# Sheet1.net
KiCad netlist of a schematic drawn in Altium Designer
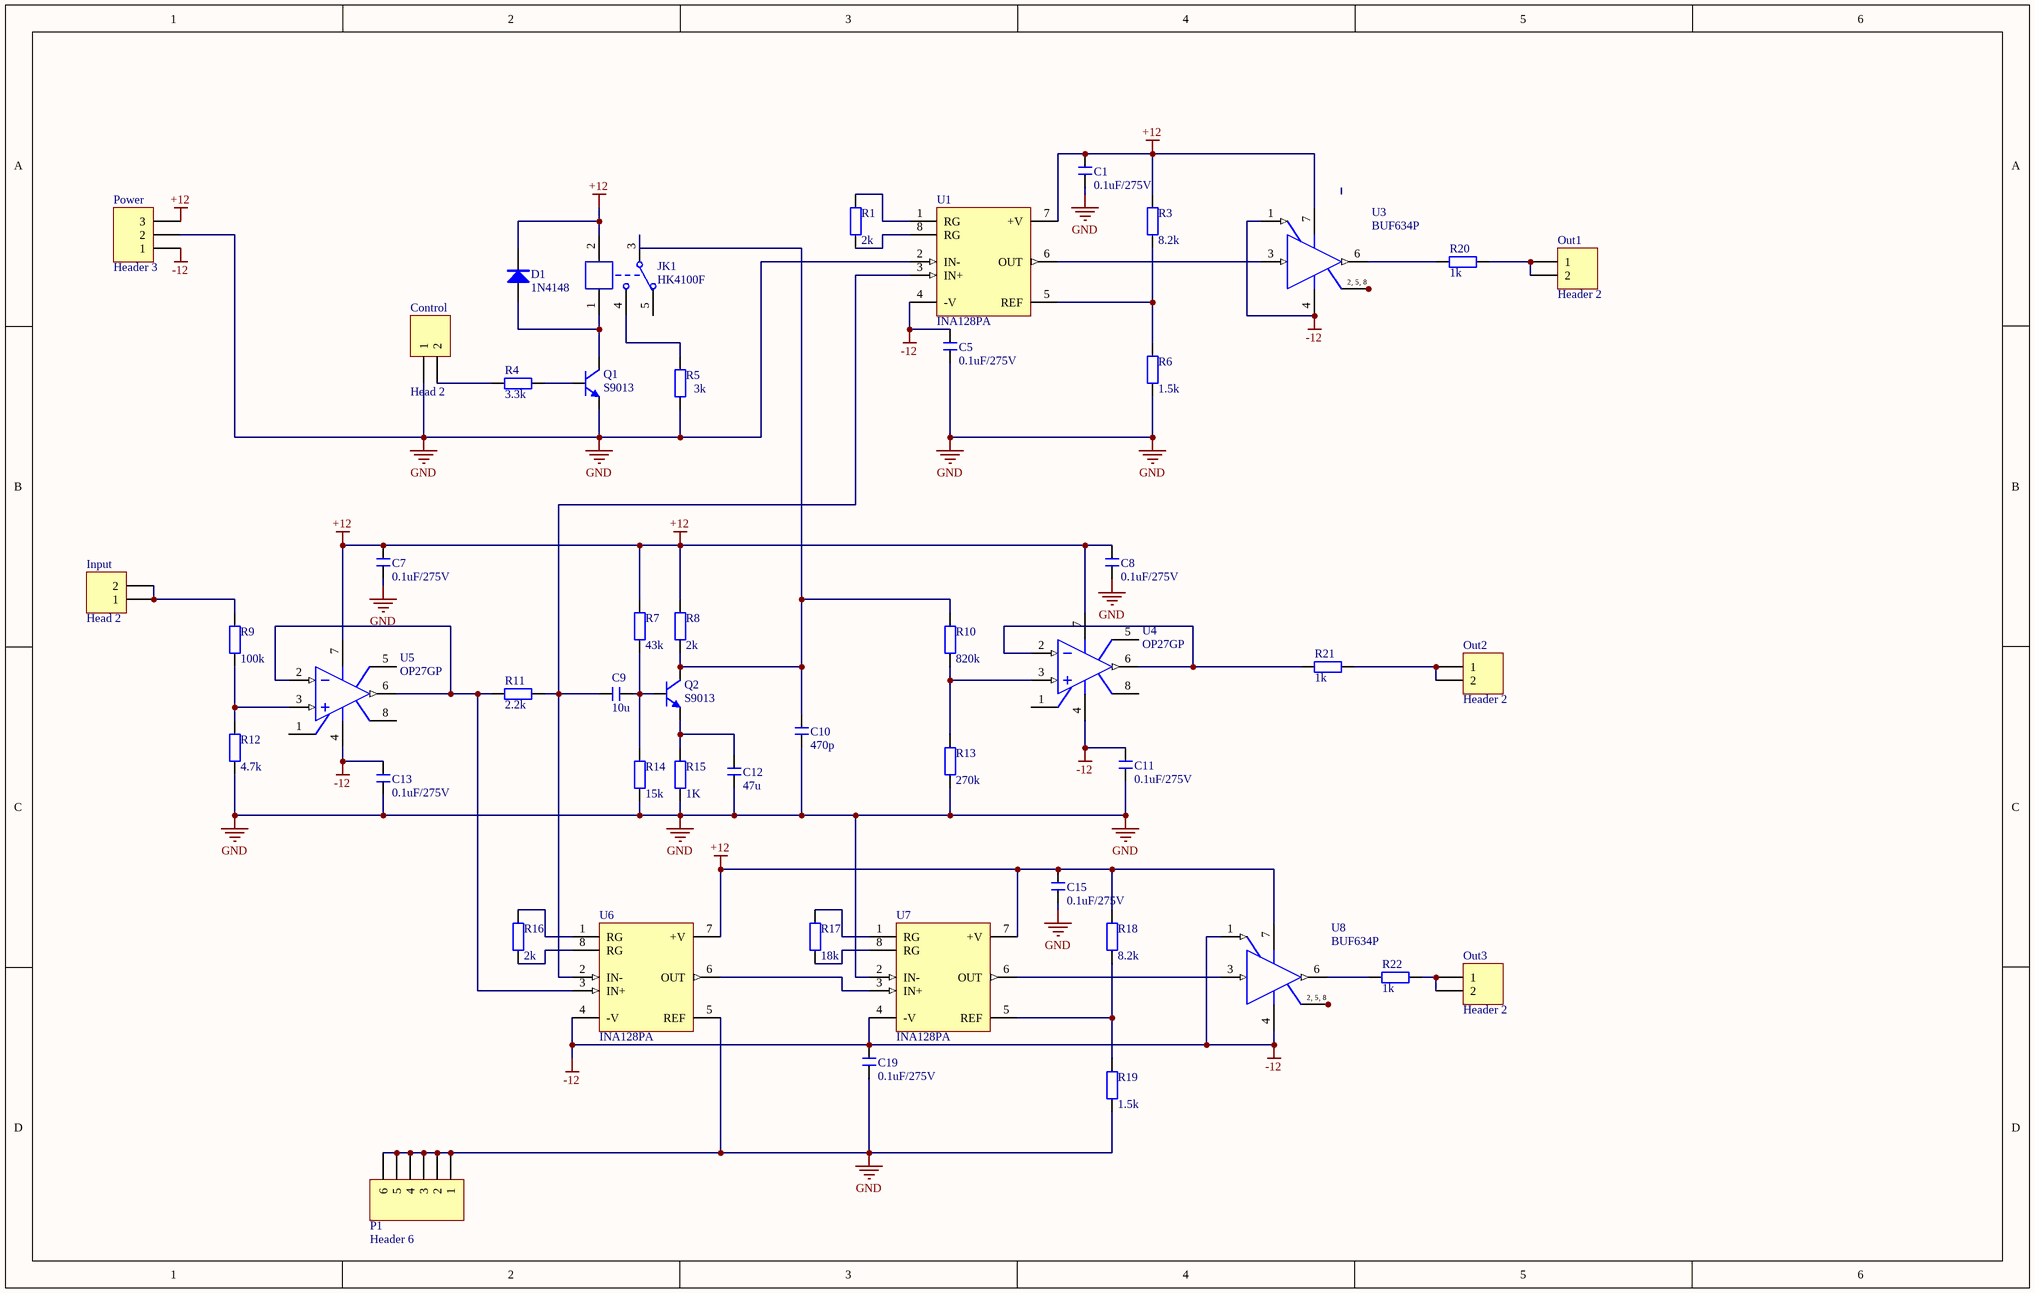
[diagram p0: Sheet1.SchDoc]

(export (version "E")
  (design (tool "Eeschema 10.0.6"))
  (components
    (comp (ref "C1")
      (value "0.1uF/275V")
      (footprint "CBB-CL71")
      (description "CBB电容")
      (fields (field (name "版权归属") "源创客"))
      (libsource (lib "3.1   - 电阻-电容-电感") (part "C-CBB"))
    )
    (comp (ref "C5")
      (value "0.1uF/275V")
      (footprint "CBB-CL71")
      (description "CBB电容")
      (fields (field (name "版权归属") "源创客"))
      (libsource (lib "3.1   - 电阻-电容-电感") (part "C-CBB"))
    )
    (comp (ref "C7")
      (value "0.1uF/275V")
      (footprint "CBB-CL71")
      (description "CBB电容")
      (fields (field (name "版权归属") "源创客"))
      (libsource (lib "3.1   - 电阻-电容-电感") (part "C-CBB"))
    )
    (comp (ref "C8")
      (value "0.1uF/275V")
      (footprint "CBB-CL71")
      (description "CBB电容")
      (fields (field (name "版权归属") "源创客"))
      (libsource (lib "3.1   - 电阻-电容-电感") (part "C-CBB"))
    )
    (comp (ref "C9")
      (value "10u")
      (footprint "CBB-CL71")
      (description "CBB电容")
      (fields (field (name "版权归属") "源创客"))
      (libsource (lib "3.1   - 电阻-电容-电感") (part "C-CBB"))
    )
    (comp (ref "C10")
      (value "470p")
      (footprint "CBB-CL71")
      (description "CBB电容")
      (fields (field (name "版权归属") "源创客"))
      (libsource (lib "3.1   - 电阻-电容-电感") (part "C-CBB"))
    )
    (comp (ref "C11")
      (value "0.1uF/275V")
      (footprint "CBB-CL71")
      (description "CBB电容")
      (fields (field (name "版权归属") "源创客"))
      (libsource (lib "3.1   - 电阻-电容-电感") (part "C-CBB"))
    )
    (comp (ref "C12")
      (value "47u")
      (footprint "CBB-CL71")
      (description "CBB电容")
      (fields (field (name "版权归属") "源创客"))
      (libsource (lib "3.1   - 电阻-电容-电感") (part "C-CBB"))
    )
    (comp (ref "C13")
      (value "0.1uF/275V")
      (footprint "CBB-CL71")
      (description "CBB电容")
      (fields (field (name "版权归属") "源创客"))
      (libsource (lib "3.1   - 电阻-电容-电感") (part "C-CBB"))
    )
    (comp (ref "C15")
      (value "0.1uF/275V")
      (footprint "CBB-CL71")
      (description "CBB电容")
      (fields (field (name "版权归属") "源创客"))
      (libsource (lib "3.1   - 电阻-电容-电感") (part "C-CBB"))
    )
    (comp (ref "C19")
      (value "0.1uF/275V")
      (footprint "CBB-CL71")
      (description "CBB电容")
      (fields (field (name "版权归属") "源创客"))
      (libsource (lib "3.1   - 电阻-电容-电感") (part "C-CBB"))
    )
    (comp (ref "Control")
      (value "Head 2")
      (footprint "HDR1X2")
      (description "Header, 2-Pin")
      (fields (field (name "PUBLISHER") "Altium Limited"))
      (libsource (lib "Miscellaneous Connectors") (part "Header 2"))
    )
    (comp (ref "D1")
      (value "1N4148")
      (footprint "DO-35")
      (description "高速开关二极管")
      (fields (field (name "版权归属") "源创客"))
      (libsource (lib "8.1   - 二极管-整流桥") (part "1N4148"))
    )
    (comp (ref "Input")
      (value "Head 2")
      (footprint "HDR1X2")
      (description "Header, 2-Pin")
      (fields (field (name "PUBLISHER") "Altium Limited"))
      (libsource (lib "") (part "Header 2_2"))
    )
    (comp (ref "JK1")
      (value "HK4100F")
      (footprint "HK4100F")
      (description "一组转换")
      (fields (field (name "版权归属") "源创客"))
      (libsource (lib "7.1   - 继电器") (part "HK4100F"))
    )
    (comp (ref "Out1")
      (value "Header 2")
      (footprint "HDR1X2")
      (description "Header, 2-Pin")
      (fields (field (name "PUBLISHER") "Altium Limited"))
      (libsource (lib "") (part "Header 2_1"))
    )
    (comp (ref "Out2")
      (value "Header 2")
      (footprint "HDR1X2")
      (description "Header, 2-Pin")
      (fields (field (name "PUBLISHER") "Altium Limited"))
      (libsource (lib "") (part "Header 2_1"))
    )
    (comp (ref "Out3")
      (value "Header 2")
      (footprint "HDR1X2")
      (description "Header, 2-Pin")
      (fields (field (name "PUBLISHER") "Altium Limited"))
      (libsource (lib "") (part "Header 2_1"))
    )
    (comp (ref "P1")
      (value "Header 6")
      (footprint "HDR1X6")
      (description "Header, 6-Pin")
      (fields (field (name "PUBLISHER") "Altium Limited"))
      (libsource (lib "Miscellaneous Connectors") (part "Header 6"))
    )
    (comp (ref "Power")
      (value "Header 3")
      (footprint "XH2.54-LI-3P")
      (description "Header, 3-Pin")
      (fields (field (name "PUBLISHER") "Altium Limited"))
      (libsource (lib "Miscellaneous Connectors") (part "Header 3"))
    )
    (comp (ref "Q1")
      (value "S9013")
      (footprint "TO92")
      (description "低频放大-NPN型")
      (fields (field (name "版权归属") "源创客"))
      (libsource (lib "6.2   - 三极管") (part "9013-DIP"))
    )
    (comp (ref "Q2")
      (value "S9013")
      (footprint "TO92")
      (description "低频放大-NPN型")
      (fields (field (name "版权归属") "源创客"))
      (libsource (lib "6.2   - 三极管") (part "9013-DIP"))
    )
    (comp (ref "R1")
      (value "2k")
      (footprint "AXIAL-0.4")
      (description "Resistor")
      (fields (field (name "PUBLISHER") "Altium Limited"))
      (libsource (lib "Miscellaneous Devices") (part "Res2"))
    )
    (comp (ref "R3")
      (value "8.2k")
      (footprint "AXIAL-0.4")
      (description "Resistor")
      (fields (field (name "PUBLISHER") "Altium Limited"))
      (libsource (lib "Miscellaneous Devices") (part "Res2"))
    )
    (comp (ref "R4")
      (value "3.3k")
      (footprint "AXIAL-0.4")
      (description "Resistor")
      (fields (field (name "PUBLISHER") "Altium Limited"))
      (libsource (lib "") (part "Res2_1"))
    )
    (comp (ref "R5")
      (value "3k")
      (footprint "AXIAL-0.4")
      (description "Resistor")
      (fields (field (name "PUBLISHER") "Altium Limited"))
      (libsource (lib "Miscellaneous Devices") (part "Res2"))
    )
    (comp (ref "R6")
      (value "1.5k")
      (footprint "AXIAL-0.4")
      (description "Resistor")
      (fields (field (name "PUBLISHER") "Altium Limited"))
      (libsource (lib "Miscellaneous Devices") (part "Res2"))
    )
    (comp (ref "R7")
      (value "43k")
      (footprint "AXIAL-0.4")
      (description "Resistor")
      (fields (field (name "PUBLISHER") "Altium Limited"))
      (libsource (lib "Miscellaneous Devices") (part "Res2"))
    )
    (comp (ref "R8")
      (value "2k")
      (footprint "AXIAL-0.4")
      (description "Resistor")
      (fields (field (name "PUBLISHER") "Altium Limited"))
      (libsource (lib "Miscellaneous Devices") (part "Res2"))
    )
    (comp (ref "R9")
      (value "100k")
      (footprint "AXIAL-0.4")
      (description "Resistor")
      (fields (field (name "PUBLISHER") "Altium Limited"))
      (libsource (lib "Miscellaneous Devices") (part "Res2"))
    )
    (comp (ref "R10")
      (value "820k")
      (footprint "AXIAL-0.4")
      (description "Resistor")
      (fields (field (name "PUBLISHER") "Altium Limited"))
      (libsource (lib "Miscellaneous Devices") (part "Res2"))
    )
    (comp (ref "R11")
      (value "2.2k")
      (footprint "AXIAL-0.4")
      (description "Resistor")
      (fields (field (name "PUBLISHER") "Altium Limited"))
      (libsource (lib "") (part "Res2_1"))
    )
    (comp (ref "R12")
      (value "4.7k")
      (footprint "AXIAL-0.4")
      (description "Resistor")
      (fields (field (name "PUBLISHER") "Altium Limited"))
      (libsource (lib "Miscellaneous Devices") (part "Res2"))
    )
    (comp (ref "R13")
      (value "270k")
      (footprint "AXIAL-0.4")
      (description "Resistor")
      (fields (field (name "PUBLISHER") "Altium Limited"))
      (libsource (lib "Miscellaneous Devices") (part "Res2"))
    )
    (comp (ref "R14")
      (value "15k")
      (footprint "AXIAL-0.4")
      (description "Resistor")
      (fields (field (name "PUBLISHER") "Altium Limited"))
      (libsource (lib "Miscellaneous Devices") (part "Res2"))
    )
    (comp (ref "R15")
      (value "1K")
      (footprint "AXIAL-0.4")
      (description "Resistor")
      (fields (field (name "PUBLISHER") "Altium Limited"))
      (libsource (lib "Miscellaneous Devices") (part "Res2"))
    )
    (comp (ref "R16")
      (value "2k")
      (footprint "AXIAL-0.4")
      (description "Resistor")
      (fields (field (name "PUBLISHER") "Altium Limited"))
      (libsource (lib "Miscellaneous Devices") (part "Res2"))
    )
    (comp (ref "R17")
      (value "18k")
      (footprint "AXIAL-0.4")
      (description "Resistor")
      (fields (field (name "PUBLISHER") "Altium Limited"))
      (libsource (lib "Miscellaneous Devices") (part "Res2"))
    )
    (comp (ref "R18")
      (value "8.2k")
      (footprint "AXIAL-0.4")
      (description "Resistor")
      (fields (field (name "PUBLISHER") "Altium Limited"))
      (libsource (lib "Miscellaneous Devices") (part "Res2"))
    )
    (comp (ref "R19")
      (value "1.5k")
      (footprint "AXIAL-0.4")
      (description "Resistor")
      (fields (field (name "PUBLISHER") "Altium Limited"))
      (libsource (lib "Miscellaneous Devices") (part "Res2"))
    )
    (comp (ref "R20")
      (value "1k")
      (footprint "AXIAL-0.4")
      (description "Resistor")
      (fields (field (name "PUBLISHER") "Altium Limited"))
      (libsource (lib "") (part "Res2_1"))
    )
    (comp (ref "R21")
      (value "1k")
      (footprint "AXIAL-0.4")
      (description "Resistor")
      (fields (field (name "PUBLISHER") "Altium Limited"))
      (libsource (lib "") (part "Res2_1"))
    )
    (comp (ref "R22")
      (value "1k")
      (footprint "AXIAL-0.4")
      (description "Resistor")
      (fields (field (name "PUBLISHER") "Altium Limited"))
      (libsource (lib "") (part "Res2_1"))
    )
    (comp (ref "U1")
      (value "INA128PA")
      (footprint "006E")
      (description "Precision, Low-Power Instrumentation Amplifiers")
      (fields (field (name "PUBLISHER") "Altium Limited"))
      (libsource (lib "BB Instrumentation Amplifier") (part "INA128PA"))
    )
    (comp (ref "U3")
      (value "BUF634P")
      (footprint "006E")
      (description "250mA High-Speed Buffer")
      (fields (field (name "PUBLISHER") "Altium Limited"))
      (libsource (lib "BB Amplifier Buffer") (part "BUF634P"))
    )
    (comp (ref "U4")
      (value "OP27GP")
      (footprint "N-8_A")
      (description "Low-Noise, Precision Operational Amplifier")
      (fields (field (name "PUBLISHER") "Altium Limited"))
      (libsource (lib "AD Operational Amplifier") (part "OP27GP"))
    )
    (comp (ref "U5")
      (value "OP27GP")
      (footprint "N-8_A")
      (description "Low-Noise, Precision Operational Amplifier")
      (fields (field (name "PUBLISHER") "Altium Limited"))
      (libsource (lib "AD Operational Amplifier") (part "OP27GP"))
    )
    (comp (ref "U6")
      (value "INA128PA")
      (footprint "006E")
      (description "Precision, Low-Power Instrumentation Amplifiers")
      (fields (field (name "PUBLISHER") "Altium Limited"))
      (libsource (lib "BB Instrumentation Amplifier") (part "INA128PA"))
    )
    (comp (ref "U7")
      (value "INA128PA")
      (footprint "006E")
      (description "Precision, Low-Power Instrumentation Amplifiers")
      (fields (field (name "PUBLISHER") "Altium Limited"))
      (libsource (lib "BB Instrumentation Amplifier") (part "INA128PA"))
    )
    (comp (ref "U8")
      (value "BUF634P")
      (footprint "006E")
      (description "250mA High-Speed Buffer")
      (fields (field (name "PUBLISHER") "Altium Limited"))
      (libsource (lib "BB Amplifier Buffer") (part "BUF634P"))
    )
  )
  (nets
    (net (code "1") (name "+12") (class "Default")
      (node (ref "C1") (pin "1") (pinfunction "1_1") (pintype "passive"))
      (node (ref "C15") (pin "1") (pinfunction "1_1") (pintype "passive"))
      (node (ref "C7") (pin "1") (pinfunction "1_1") (pintype "passive"))
      (node (ref "C8") (pin "1") (pinfunction "1_1") (pintype "passive"))
      (node (ref "D1") (pin "2") (pinfunction "K_2") (pintype "passive"))
      (node (ref "JK1") (pin "2") (pinfunction "2_2") (pintype "passive"))
      (node (ref "Power") (pin "3") (pinfunction "3_3") (pintype "passive"))
      (node (ref "R18") (pin "2") (pinfunction "2_2") (pintype "passive"))
      (node (ref "R3") (pin "2") (pinfunction "2_2") (pintype "passive"))
      (node (ref "R7") (pin "2") (pinfunction "2_2") (pintype "passive"))
      (node (ref "R8") (pin "2") (pinfunction "2_2") (pintype "passive"))
      (node (ref "U1") (pin "7") (pinfunction "+V_7") (pintype "power_in"))
      (node (ref "U3") (pin "7") (pinfunction "V+_7") (pintype "power_in"))
      (node (ref "U4") (pin "7") (pinfunction "V+_7") (pintype "power_in"))
      (node (ref "U5") (pin "7") (pinfunction "V+_7") (pintype "power_in"))
      (node (ref "U6") (pin "7") (pinfunction "+V_7") (pintype "power_in"))
      (node (ref "U7") (pin "7") (pinfunction "+V_7") (pintype "power_in"))
      (node (ref "U8") (pin "7") (pinfunction "V+_7") (pintype "power_in"))
    )
    (net (code "2") (name "-12") (class "Default")
      (node (ref "C11") (pin "1") (pinfunction "1_1") (pintype "passive"))
      (node (ref "C13") (pin "1") (pinfunction "1_1") (pintype "passive"))
      (node (ref "C19") (pin "1") (pinfunction "1_1") (pintype "passive"))
      (node (ref "C5") (pin "1") (pinfunction "1_1") (pintype "passive"))
      (node (ref "Power") (pin "1") (pinfunction "1_1") (pintype "passive"))
      (node (ref "U1") (pin "4") (pinfunction "-V_4") (pintype "power_in"))
      (node (ref "U3") (pin "1") (pinfunction "BW_1") (pintype "input"))
      (node (ref "U3") (pin "4") (pinfunction "V-_4") (pintype "power_in"))
      (node (ref "U4") (pin "4") (pinfunction "V-_4") (pintype "power_in"))
      (node (ref "U5") (pin "4") (pinfunction "V-_4") (pintype "power_in"))
      (node (ref "U6") (pin "4") (pinfunction "-V_4") (pintype "power_in"))
      (node (ref "U7") (pin "4") (pinfunction "-V_4") (pintype "power_in"))
      (node (ref "U8") (pin "1") (pinfunction "BW_1") (pintype "input"))
      (node (ref "U8") (pin "4") (pinfunction "V-_4") (pintype "power_in"))
    )
    (net (code "3") (name "GND") (class "Default")
      (node (ref "C1") (pin "2") (pinfunction "2_2") (pintype "passive"))
      (node (ref "C10") (pin "1") (pinfunction "1_1") (pintype "passive"))
      (node (ref "C11") (pin "2") (pinfunction "2_2") (pintype "passive"))
      (node (ref "C12") (pin "1") (pinfunction "1_1") (pintype "passive"))
      (node (ref "C13") (pin "2") (pinfunction "2_2") (pintype "passive"))
      (node (ref "C15") (pin "2") (pinfunction "2_2") (pintype "passive"))
      (node (ref "C19") (pin "2") (pinfunction "2_2") (pintype "passive"))
      (node (ref "C5") (pin "2") (pinfunction "2_2") (pintype "passive"))
      (node (ref "C7") (pin "2") (pinfunction "2_2") (pintype "passive"))
      (node (ref "C8") (pin "2") (pinfunction "2_2") (pintype "passive"))
      (node (ref "Control") (pin "1") (pinfunction "1_1") (pintype "passive"))
      (node (ref "P1") (pin "1") (pinfunction "1_1") (pintype "passive"))
      (node (ref "P1") (pin "2") (pinfunction "2_2") (pintype "passive"))
      (node (ref "P1") (pin "3") (pinfunction "3_3") (pintype "passive"))
      (node (ref "P1") (pin "4") (pinfunction "4_4") (pintype "passive"))
      (node (ref "P1") (pin "5") (pinfunction "5_5") (pintype "passive"))
      (node (ref "P1") (pin "6") (pinfunction "6_6") (pintype "passive"))
      (node (ref "Power") (pin "2") (pinfunction "2_2") (pintype "passive"))
      (node (ref "Q1") (pin "1") (pinfunction "E_1") (pintype "passive"))
      (node (ref "R12") (pin "1") (pinfunction "1_1") (pintype "passive"))
      (node (ref "R13") (pin "1") (pinfunction "1_1") (pintype "passive"))
      (node (ref "R14") (pin "1") (pinfunction "1_1") (pintype "passive"))
      (node (ref "R15") (pin "1") (pinfunction "1_1") (pintype "passive"))
      (node (ref "R19") (pin "1") (pinfunction "1_1") (pintype "passive"))
      (node (ref "R5") (pin "1") (pinfunction "1_1") (pintype "passive"))
      (node (ref "R6") (pin "1") (pinfunction "1_1") (pintype "passive"))
      (node (ref "U1") (pin "2") (pinfunction "IN-_2") (pintype "input"))
      (node (ref "U6") (pin "5") (pinfunction "REF_5") (pintype "passive"))
      (node (ref "U7") (pin "2") (pinfunction "IN-_2") (pintype "input"))
    )
    (net (code "4") (name "Net-(Control-Pad2)") (class "Default")
      (node (ref "Control") (pin "2") (pinfunction "2_2") (pintype "passive"))
      (node (ref "R4") (pin "2") (pinfunction "2_2") (pintype "passive"))
    )
    (net (code "5") (name "Net-(D1-A)") (class "Default")
      (node (ref "D1") (pin "1") (pinfunction "A_1") (pintype "passive"))
      (node (ref "JK1") (pin "1") (pinfunction "1_1") (pintype "passive"))
      (node (ref "Q1") (pin "3") (pinfunction "C_3") (pintype "passive"))
    )
    (net (code "6") (name "Net-(Input-Pad1)") (class "Default")
      (node (ref "Input") (pin "1") (pinfunction "1_1") (pintype "passive"))
      (node (ref "Input") (pin "2") (pinfunction "2_2") (pintype "passive"))
      (node (ref "R9") (pin "2") (pinfunction "2_2") (pintype "passive"))
    )
    (net (code "7") (name "Net-(JK1-Pad4)") (class "Default")
      (node (ref "JK1") (pin "4") (pinfunction "4_4") (pintype "passive"))
      (node (ref "R5") (pin "2") (pinfunction "2_2") (pintype "passive"))
    )
    (net (code "8") (name "Net-(Out1-Pad1)") (class "Default")
      (node (ref "Out1") (pin "1") (pinfunction "1_1") (pintype "passive"))
      (node (ref "Out1") (pin "2") (pinfunction "2_2") (pintype "passive"))
      (node (ref "R20") (pin "1") (pinfunction "1_1") (pintype "passive"))
    )
    (net (code "9") (name "Net-(Out2-Pad1)") (class "Default")
      (node (ref "Out2") (pin "1") (pinfunction "1_1") (pintype "passive"))
      (node (ref "Out2") (pin "2") (pinfunction "2_2") (pintype "passive"))
      (node (ref "R21") (pin "1") (pinfunction "1_1") (pintype "passive"))
    )
    (net (code "10") (name "Net-(Out3-Pad1)") (class "Default")
      (node (ref "Out3") (pin "1") (pinfunction "1_1") (pintype "passive"))
      (node (ref "Out3") (pin "2") (pinfunction "2_2") (pintype "passive"))
      (node (ref "R22") (pin "1") (pinfunction "1_1") (pintype "passive"))
    )
    (net (code "11") (name "Net-(Q1-B)") (class "Default")
      (node (ref "Q1") (pin "2") (pinfunction "B_2") (pintype "passive"))
      (node (ref "R4") (pin "1") (pinfunction "1_1") (pintype "passive"))
    )
    (net (code "12") (name "Net-(Q2-B)") (class "Default")
      (node (ref "C9") (pin "2") (pinfunction "2_2") (pintype "passive"))
      (node (ref "Q2") (pin "2") (pinfunction "B_2") (pintype "passive"))
      (node (ref "R14") (pin "2") (pinfunction "2_2") (pintype "passive"))
      (node (ref "R7") (pin "1") (pinfunction "1_1") (pintype "passive"))
    )
    (net (code "13") (name "Net-(Q2-C)") (class "Default")
      (node (ref "C10") (pin "2") (pinfunction "2_2") (pintype "passive"))
      (node (ref "JK1") (pin "3") (pinfunction "3_3") (pintype "passive"))
      (node (ref "Q2") (pin "3") (pinfunction "C_3") (pintype "passive"))
      (node (ref "R10") (pin "2") (pinfunction "2_2") (pintype "passive"))
      (node (ref "R8") (pin "1") (pinfunction "1_1") (pintype "passive"))
    )
    (net (code "14") (name "Net-(Q2-E)") (class "Default")
      (node (ref "C12") (pin "2") (pinfunction "2_2") (pintype "passive"))
      (node (ref "Q2") (pin "1") (pinfunction "E_1") (pintype "passive"))
      (node (ref "R15") (pin "2") (pinfunction "2_2") (pintype "passive"))
    )
    (net (code "15") (name "Net-(R1-Pad1)") (class "Default")
      (node (ref "R1") (pin "1") (pinfunction "1_1") (pintype "passive"))
      (node (ref "U1") (pin "8") (pinfunction "RG_8") (pintype "passive"))
    )
    (net (code "16") (name "Net-(R1-Pad2)") (class "Default")
      (node (ref "R1") (pin "2") (pinfunction "2_2") (pintype "passive"))
      (node (ref "U1") (pin "1") (pinfunction "RG_1") (pintype "passive"))
    )
    (net (code "17") (name "Net-(R16-Pad1)") (class "Default")
      (node (ref "R16") (pin "1") (pinfunction "1_1") (pintype "passive"))
      (node (ref "U6") (pin "8") (pinfunction "RG_8") (pintype "passive"))
    )
    (net (code "18") (name "Net-(R16-Pad2)") (class "Default")
      (node (ref "R16") (pin "2") (pinfunction "2_2") (pintype "passive"))
      (node (ref "U6") (pin "1") (pinfunction "RG_1") (pintype "passive"))
    )
    (net (code "19") (name "Net-(R17-Pad1)") (class "Default")
      (node (ref "R17") (pin "1") (pinfunction "1_1") (pintype "passive"))
      (node (ref "U7") (pin "8") (pinfunction "RG_8") (pintype "passive"))
    )
    (net (code "20") (name "Net-(R17-Pad2)") (class "Default")
      (node (ref "R17") (pin "2") (pinfunction "2_2") (pintype "passive"))
      (node (ref "U7") (pin "1") (pinfunction "RG_1") (pintype "passive"))
    )
    (net (code "21") (name "Net-(U1-IN+)") (class "Default")
      (node (ref "C9") (pin "1") (pinfunction "1_1") (pintype "passive"))
      (node (ref "R11") (pin "1") (pinfunction "1_1") (pintype "passive"))
      (node (ref "U1") (pin "3") (pinfunction "IN+_3") (pintype "input"))
      (node (ref "U6") (pin "2") (pinfunction "IN-_2") (pintype "input"))
    )
    (net (code "22") (name "Net-(U1-OUT)") (class "Default")
      (node (ref "U1") (pin "6") (pinfunction "OUT_6") (pintype "output"))
      (node (ref "U3") (pin "3") (pinfunction "IN_3") (pintype "input"))
    )
    (net (code "23") (name "Net-(U1-REF)") (class "Default")
      (node (ref "R3") (pin "1") (pinfunction "1_1") (pintype "passive"))
      (node (ref "R6") (pin "2") (pinfunction "2_2") (pintype "passive"))
      (node (ref "U1") (pin "5") (pinfunction "REF_5") (pintype "passive"))
    )
    (net (code "24") (name "Net-(U3-NC-Pad2)") (class "Default")
      (node (ref "U3") (pin "2") (pinfunction "NC_2") (pintype "passive"))
      (node (ref "U3") (pin "5") (pinfunction "NC_5") (pintype "passive"))
      (node (ref "U3") (pin "8") (pinfunction "NC_8") (pintype "passive"))
    )
    (net (code "25") (name "Net-(U3-OUT)") (class "Default")
      (node (ref "R20") (pin "2") (pinfunction "2_2") (pintype "passive"))
      (node (ref "U3") (pin "6") (pinfunction "OUT_6") (pintype "output"))
    )
    (net (code "26") (name "Net-(U4-IN+)") (class "Default")
      (node (ref "R10") (pin "1") (pinfunction "1_1") (pintype "passive"))
      (node (ref "R13") (pin "2") (pinfunction "2_2") (pintype "passive"))
      (node (ref "U4") (pin "3") (pinfunction "IN+_3") (pintype "input"))
    )
    (net (code "27") (name "Net-(U4-IN-)") (class "Default")
      (node (ref "R21") (pin "2") (pinfunction "2_2") (pintype "passive"))
      (node (ref "U4") (pin "2") (pinfunction "IN-_2") (pintype "input"))
      (node (ref "U4") (pin "6") (pinfunction "OUT_6") (pintype "output"))
    )
    (net (code "28") (name "Net-(U5-IN+)") (class "Default")
      (node (ref "R12") (pin "2") (pinfunction "2_2") (pintype "passive"))
      (node (ref "R9") (pin "1") (pinfunction "1_1") (pintype "passive"))
      (node (ref "U5") (pin "3") (pinfunction "IN+_3") (pintype "input"))
    )
    (net (code "29") (name "Net-(U5-IN-)") (class "Default")
      (node (ref "R11") (pin "2") (pinfunction "2_2") (pintype "passive"))
      (node (ref "U5") (pin "2") (pinfunction "IN-_2") (pintype "input"))
      (node (ref "U5") (pin "6") (pinfunction "OUT_6") (pintype "output"))
      (node (ref "U6") (pin "3") (pinfunction "IN+_3") (pintype "input"))
    )
    (net (code "30") (name "Net-(U6-OUT)") (class "Default")
      (node (ref "U6") (pin "6") (pinfunction "OUT_6") (pintype "output"))
      (node (ref "U7") (pin "3") (pinfunction "IN+_3") (pintype "input"))
    )
    (net (code "31") (name "Net-(U7-OUT)") (class "Default")
      (node (ref "U7") (pin "6") (pinfunction "OUT_6") (pintype "output"))
      (node (ref "U8") (pin "3") (pinfunction "IN_3") (pintype "input"))
    )
    (net (code "32") (name "Net-(U7-REF)") (class "Default")
      (node (ref "R18") (pin "1") (pinfunction "1_1") (pintype "passive"))
      (node (ref "R19") (pin "2") (pinfunction "2_2") (pintype "passive"))
      (node (ref "U7") (pin "5") (pinfunction "REF_5") (pintype "passive"))
    )
    (net (code "33") (name "Net-(U8-NC-Pad2)") (class "Default")
      (node (ref "U8") (pin "2") (pinfunction "NC_2") (pintype "passive"))
      (node (ref "U8") (pin "5") (pinfunction "NC_5") (pintype "passive"))
      (node (ref "U8") (pin "8") (pinfunction "NC_8") (pintype "passive"))
    )
    (net (code "34") (name "Net-(U8-OUT)") (class "Default")
      (node (ref "R22") (pin "2") (pinfunction "2_2") (pintype "passive"))
      (node (ref "U8") (pin "6") (pinfunction "OUT_6") (pintype "output"))
    )
    (net (code "35") (name "unconnected-(JK1-Pad5)") (class "Default")
      (node (ref "JK1") (pin "5") (pinfunction "5_5") (pintype "passive"))
    )
    (net (code "36") (name "unconnected-(U4-CMPEN-Pad1)") (class "Default")
      (node (ref "U4") (pin "1") (pinfunction "CMPEN_1") (pintype "passive"))
    )
    (net (code "37") (name "unconnected-(U4-CMPEN-Pad8)") (class "Default")
      (node (ref "U4") (pin "8") (pinfunction "CMPEN_8") (pintype "passive"))
    )
    (net (code "38") (name "unconnected-(U4-NC-Pad5)") (class "Default")
      (node (ref "U4") (pin "5") (pinfunction "NC_5") (pintype "passive"))
    )
    (net (code "39") (name "unconnected-(U5-CMPEN-Pad1)") (class "Default")
      (node (ref "U5") (pin "1") (pinfunction "CMPEN_1") (pintype "passive"))
    )
    (net (code "40") (name "unconnected-(U5-CMPEN-Pad8)") (class "Default")
      (node (ref "U5") (pin "8") (pinfunction "CMPEN_8") (pintype "passive"))
    )
    (net (code "41") (name "unconnected-(U5-NC-Pad5)") (class "Default")
      (node (ref "U5") (pin "5") (pinfunction "NC_5") (pintype "passive"))
    )
  )
)
